# PLD_Photodiodes.net
KiCad netlist of a schematic drawn in Altium Designer
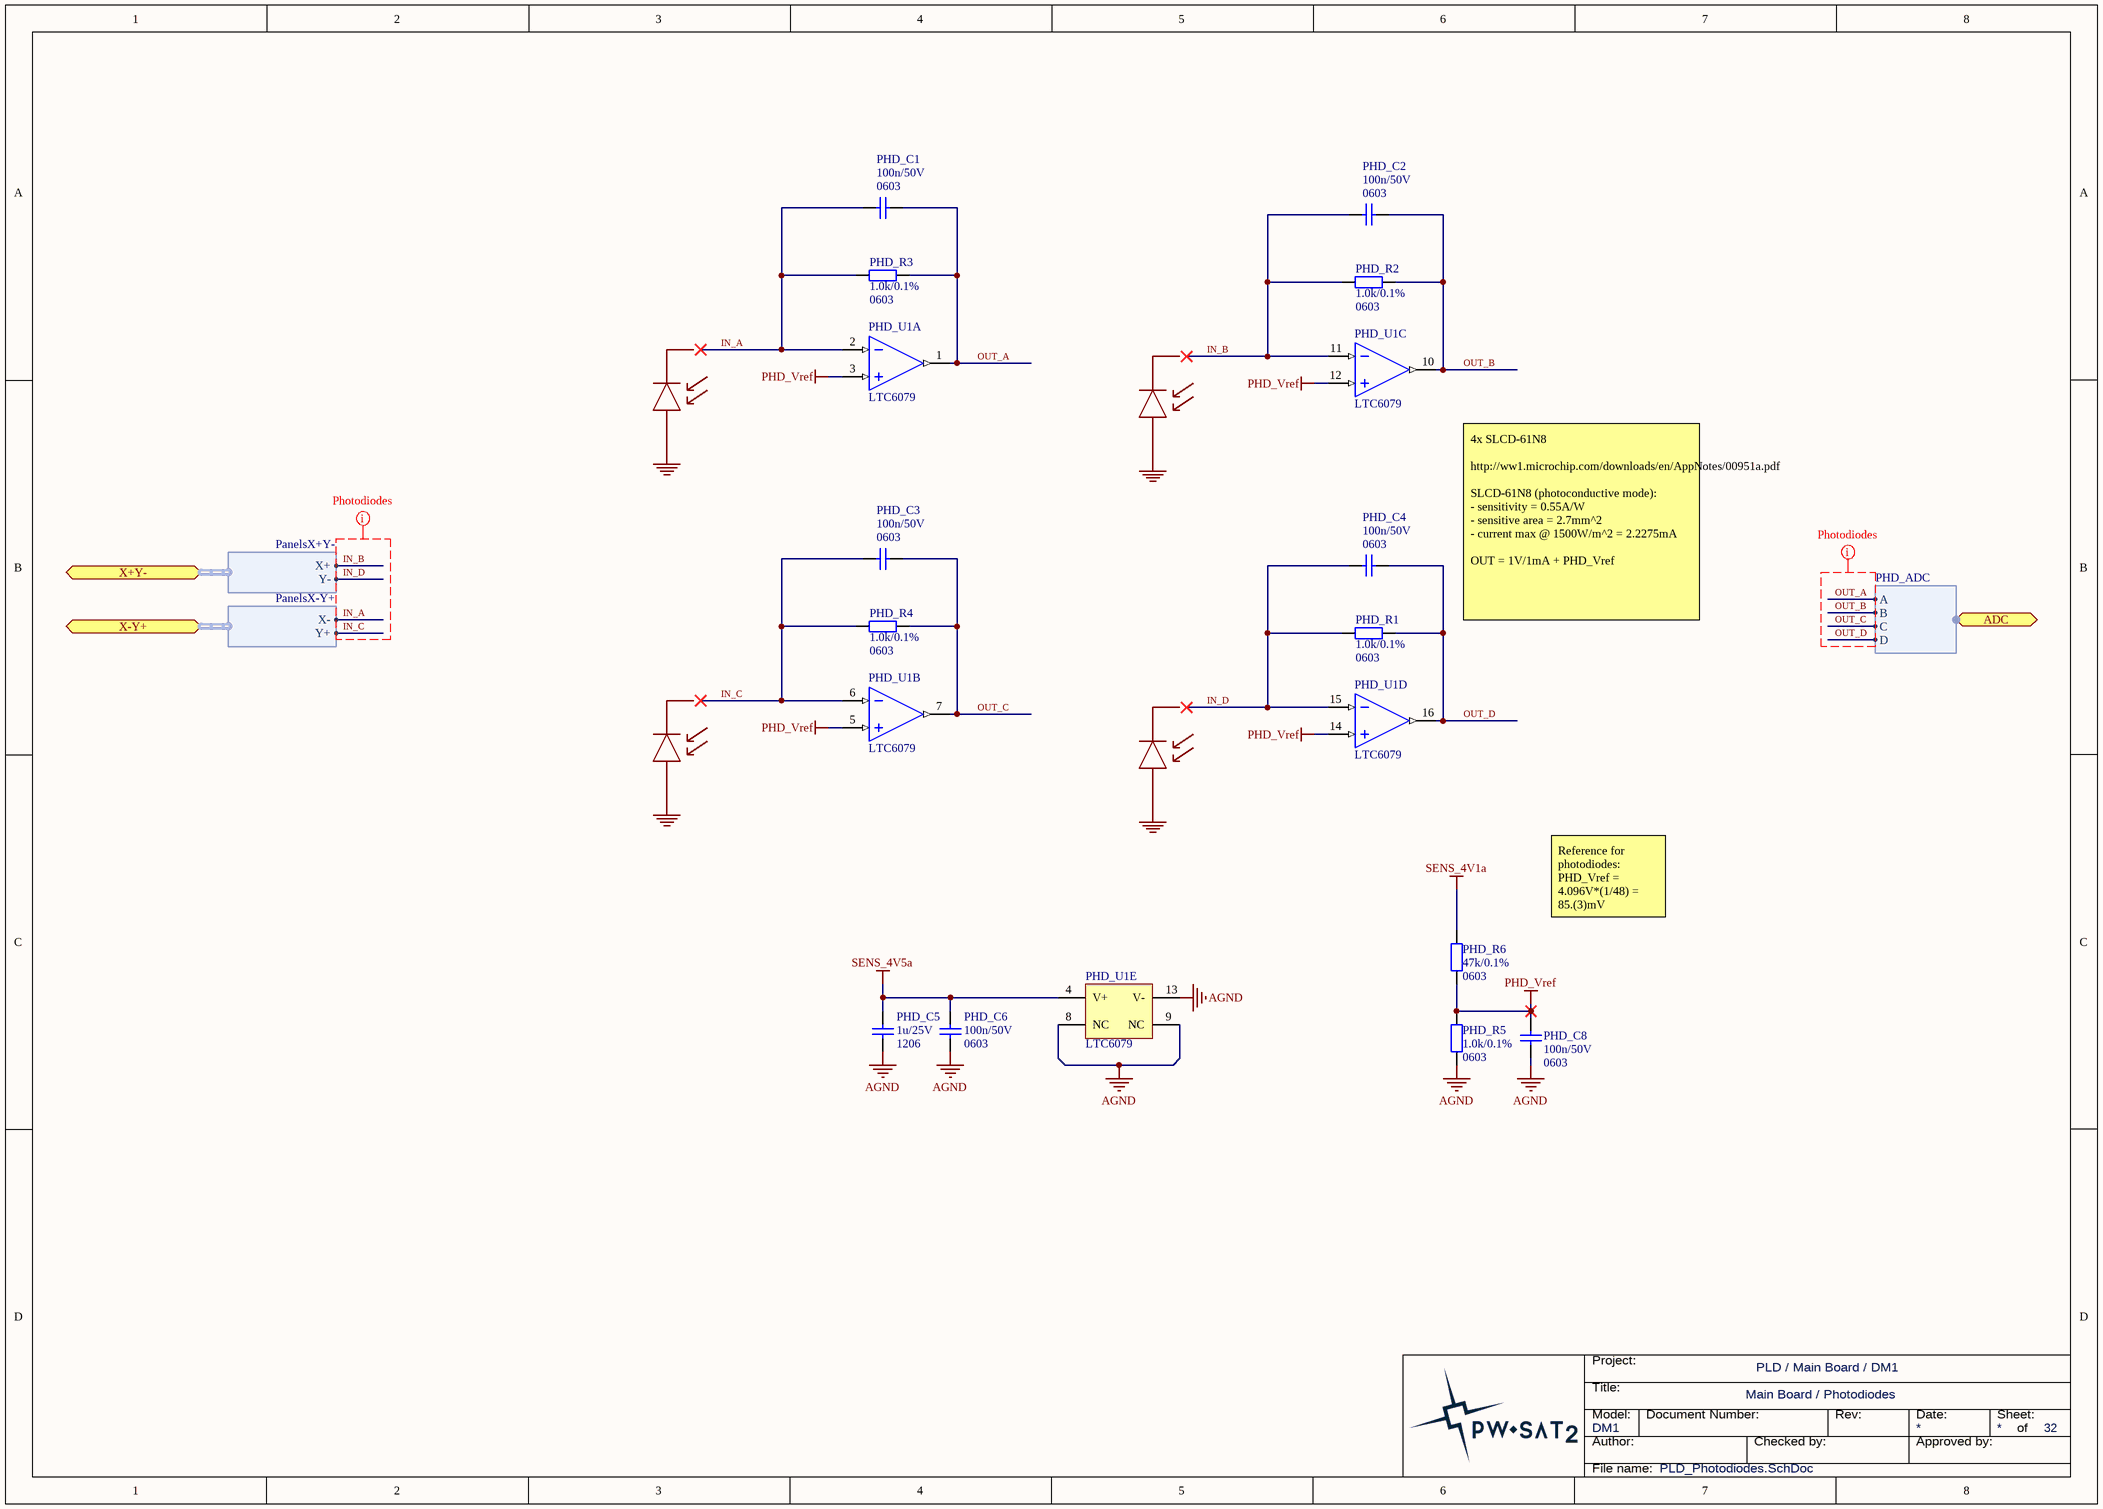
[diagram p0: PLD_Photodiodes.SchDoc]

(export (version "E")
  (design (tool "Eeschema 10.0.6"))
  (components
    (comp (ref "PHD_C1")
      (value "100n/50V")
      (footprint "SMD_Capacitor_0603")
      (description "Ceramic Cap Kemet COTS 100n/50V X7R 0603")
      (fields
        (field (name "MANUFACTURER") "Kemet")
        (field (name "MANUFACTURERPARTNUMBER") "C0603T104K5RALTU")
        (field (name "PACKAGE") "0603")
      )
      (libsource (lib "capacitors") (part "Cer_C0603T104K5RALTU"))
    )
    (comp (ref "PHD_C2")
      (value "100n/50V")
      (footprint "SMD_Capacitor_0603")
      (description "Ceramic Cap Kemet COTS 100n/50V X7R 0603")
      (fields
        (field (name "MANUFACTURER") "Kemet")
        (field (name "MANUFACTURERPARTNUMBER") "C0603T104K5RALTU")
        (field (name "PACKAGE") "0603")
      )
      (libsource (lib "capacitors") (part "Cer_C0603T104K5RALTU"))
    )
    (comp (ref "PHD_C3")
      (value "100n/50V")
      (footprint "SMD_Capacitor_0603")
      (description "Ceramic Cap Kemet COTS 100n/50V X7R 0603")
      (fields
        (field (name "MANUFACTURER") "Kemet")
        (field (name "MANUFACTURERPARTNUMBER") "C0603T104K5RALTU")
        (field (name "PACKAGE") "0603")
      )
      (libsource (lib "capacitors") (part "Cer_C0603T104K5RALTU"))
    )
    (comp (ref "PHD_C4")
      (value "100n/50V")
      (footprint "SMD_Capacitor_0603")
      (description "Ceramic Cap Kemet COTS 100n/50V X7R 0603")
      (fields
        (field (name "MANUFACTURER") "Kemet")
        (field (name "MANUFACTURERPARTNUMBER") "C0603T104K5RALTU")
        (field (name "PACKAGE") "0603")
      )
      (libsource (lib "capacitors") (part "Cer_C0603T104K5RALTU"))
    )
    (comp (ref "PHD_C5")
      (value "1u/25V")
      (footprint "SMD_Capacitor_1206")
      (description "Ceramic Cap Kemet COTS 1u/25V X7R 1206")
      (fields
        (field (name "MANUFACTURERPARTNUMBER") "C1206T105K3RALTU")
        (field (name "MANUFACTURER") "Kemet")
        (field (name "PACKAGE") "1206")
      )
      (libsource (lib "capacitors") (part "Cer_C1206T105K3RALTU"))
    )
    (comp (ref "PHD_C6")
      (value "100n/50V")
      (footprint "SMD_Capacitor_0603")
      (description "Ceramic Cap Kemet COTS 100n/50V X7R 0603")
      (fields
        (field (name "MANUFACTURER") "Kemet")
        (field (name "MANUFACTURERPARTNUMBER") "C0603T104K5RALTU")
        (field (name "PACKAGE") "0603")
      )
      (libsource (lib "capacitors") (part "Cer_C0603T104K5RALTU"))
    )
    (comp (ref "PHD_C8")
      (value "100n/50V")
      (footprint "SMD_Capacitor_0603")
      (description "Ceramic Cap Kemet COTS 100n/50V X7R 0603")
      (fields
        (field (name "MANUFACTURER") "Kemet")
        (field (name "MANUFACTURERPARTNUMBER") "C0603T104K5RALTU")
        (field (name "PACKAGE") "0603")
      )
      (libsource (lib "capacitors") (part "Cer_C0603T104K5RALTU"))
    )
    (comp (ref "PHD_R1")
      (value "1.0k/0.1%")
      (footprint "SMD_Resistor_0603")
      (fields (field (name "PACKAGE") "0603"))
      (libsource (lib "") (part "Res_1"))
    )
    (comp (ref "PHD_R2")
      (value "1.0k/0.1%")
      (footprint "SMD_Resistor_0603")
      (fields (field (name "PACKAGE") "0603"))
      (libsource (lib "") (part "Res_1"))
    )
    (comp (ref "PHD_R3")
      (value "1.0k/0.1%")
      (footprint "SMD_Resistor_0603")
      (fields (field (name "PACKAGE") "0603"))
      (libsource (lib "") (part "Res_1"))
    )
    (comp (ref "PHD_R4")
      (value "1.0k/0.1%")
      (footprint "SMD_Resistor_0603")
      (fields (field (name "PACKAGE") "0603"))
      (libsource (lib "") (part "Res_1"))
    )
    (comp (ref "PHD_R5")
      (value "1.0k/0.1%")
      (footprint "SMD_Resistor_0603")
      (fields (field (name "PACKAGE") "0603"))
      (libsource (lib "resistors") (part "Res"))
    )
    (comp (ref "PHD_R6")
      (value "47k/0.1%")
      (footprint "SMD_Resistor_0603")
      (fields (field (name "PACKAGE") "0603"))
      (libsource (lib "resistors") (part "Res"))
    )
    (comp (ref "PHD_U1")
      (value "LTC6079")
      (footprint "SSOP-16")
      (description "Rail-to-rail, quad operational amplifier. Library compatible with LTC608X LTC607X op-amps")
      (fields (field (name "MANUFACTURER") "Linear Technology"))
      (libsource (lib "microcircuits") (part "LTC6079"))
    )
  )
  (nets
    (net (code "4") (name "/IN_A") (class "Default")
      (node (ref "PHD_C1") (pin "1") (pinfunction "1_1") (pintype "passive"))
      (node (ref "PHD_R3") (pin "1") (pinfunction "1_1") (pintype "passive"))
      (node (ref "PHD_U1") (pin "2") (pinfunction "IN-_A_2") (pintype "input"))
    )
    (net (code "5") (name "/IN_B") (class "Default")
      (node (ref "PHD_C2") (pin "1") (pinfunction "1_1") (pintype "passive"))
      (node (ref "PHD_R2") (pin "1") (pinfunction "1_1") (pintype "passive"))
      (node (ref "PHD_U1") (pin "11") (pinfunction "IN-_C_11") (pintype "input"))
    )
    (net (code "6") (name "/IN_C") (class "Default")
      (node (ref "PHD_C3") (pin "1") (pinfunction "1_1") (pintype "passive"))
      (node (ref "PHD_R4") (pin "1") (pinfunction "1_1") (pintype "passive"))
      (node (ref "PHD_U1") (pin "6") (pinfunction "IN-_B_6") (pintype "input"))
    )
    (net (code "7") (name "/IN_D") (class "Default")
      (node (ref "PHD_C4") (pin "1") (pinfunction "1_1") (pintype "passive"))
      (node (ref "PHD_R1") (pin "1") (pinfunction "1_1") (pintype "passive"))
      (node (ref "PHD_U1") (pin "15") (pinfunction "IN-_D_15") (pintype "input"))
    )
    (net (code "8") (name "/OUT_A") (class "Default")
      (node (ref "PHD_C1") (pin "2") (pinfunction "2_2") (pintype "passive"))
      (node (ref "PHD_R3") (pin "2") (pinfunction "2_2") (pintype "passive"))
      (node (ref "PHD_U1") (pin "1") (pinfunction "OUT_A_1") (pintype "output"))
    )
    (net (code "9") (name "/OUT_B") (class "Default")
      (node (ref "PHD_C2") (pin "2") (pinfunction "2_2") (pintype "passive"))
      (node (ref "PHD_R2") (pin "2") (pinfunction "2_2") (pintype "passive"))
      (node (ref "PHD_U1") (pin "10") (pinfunction "OUT_C_10") (pintype "output"))
    )
    (net (code "10") (name "/OUT_C") (class "Default")
      (node (ref "PHD_C3") (pin "2") (pinfunction "2_2") (pintype "passive"))
      (node (ref "PHD_R4") (pin "2") (pinfunction "2_2") (pintype "passive"))
      (node (ref "PHD_U1") (pin "7") (pinfunction "OUT_B_7") (pintype "output"))
    )
    (net (code "11") (name "/OUT_D") (class "Default")
      (node (ref "PHD_C4") (pin "2") (pinfunction "2_2") (pintype "passive"))
      (node (ref "PHD_R1") (pin "2") (pinfunction "2_2") (pintype "passive"))
      (node (ref "PHD_U1") (pin "16") (pinfunction "OUT_D_16") (pintype "output"))
    )
    (net (code "15") (name "AGND") (class "Default")
      (node (ref "PHD_C5") (pin "2") (pinfunction "2_2") (pintype "passive"))
      (node (ref "PHD_C6") (pin "1") (pinfunction "1_1") (pintype "passive"))
      (node (ref "PHD_C8") (pin "2") (pinfunction "2_2") (pintype "passive"))
      (node (ref "PHD_R5") (pin "2") (pinfunction "2_2") (pintype "passive"))
      (node (ref "PHD_U1") (pin "13") (pinfunction "V-_13") (pintype "power_in"))
      (node (ref "PHD_U1") (pin "8") (pinfunction "NC_8") (pintype "passive"))
      (node (ref "PHD_U1") (pin "9") (pinfunction "NC_9") (pintype "passive"))
    )
    (net (code "16") (name "PHD_Vref") (class "Default")
      (node (ref "PHD_C8") (pin "1") (pinfunction "1_1") (pintype "passive"))
      (node (ref "PHD_R5") (pin "1") (pinfunction "1_1") (pintype "passive"))
      (node (ref "PHD_R6") (pin "2") (pinfunction "2_2") (pintype "passive"))
      (node (ref "PHD_U1") (pin "12") (pinfunction "IN+_C_12") (pintype "input"))
      (node (ref "PHD_U1") (pin "14") (pinfunction "IN+_D_14") (pintype "input"))
      (node (ref "PHD_U1") (pin "3") (pinfunction "IN+_A_3") (pintype "input"))
      (node (ref "PHD_U1") (pin "5") (pinfunction "IN+_B_5") (pintype "input"))
    )
    (net (code "17") (name "SENS_4V1a") (class "Default")
      (node (ref "PHD_R6") (pin "1") (pinfunction "1_1") (pintype "passive"))
    )
    (net (code "18") (name "SENS_4V5a") (class "Default")
      (node (ref "PHD_C5") (pin "1") (pinfunction "1_1") (pintype "passive"))
      (node (ref "PHD_C6") (pin "2") (pinfunction "2_2") (pintype "passive"))
      (node (ref "PHD_U1") (pin "4") (pinfunction "V+_4") (pintype "power_in"))
    )
  )
)
